# Power.net
KiCad netlist of a schematic drawn in Altium Designer
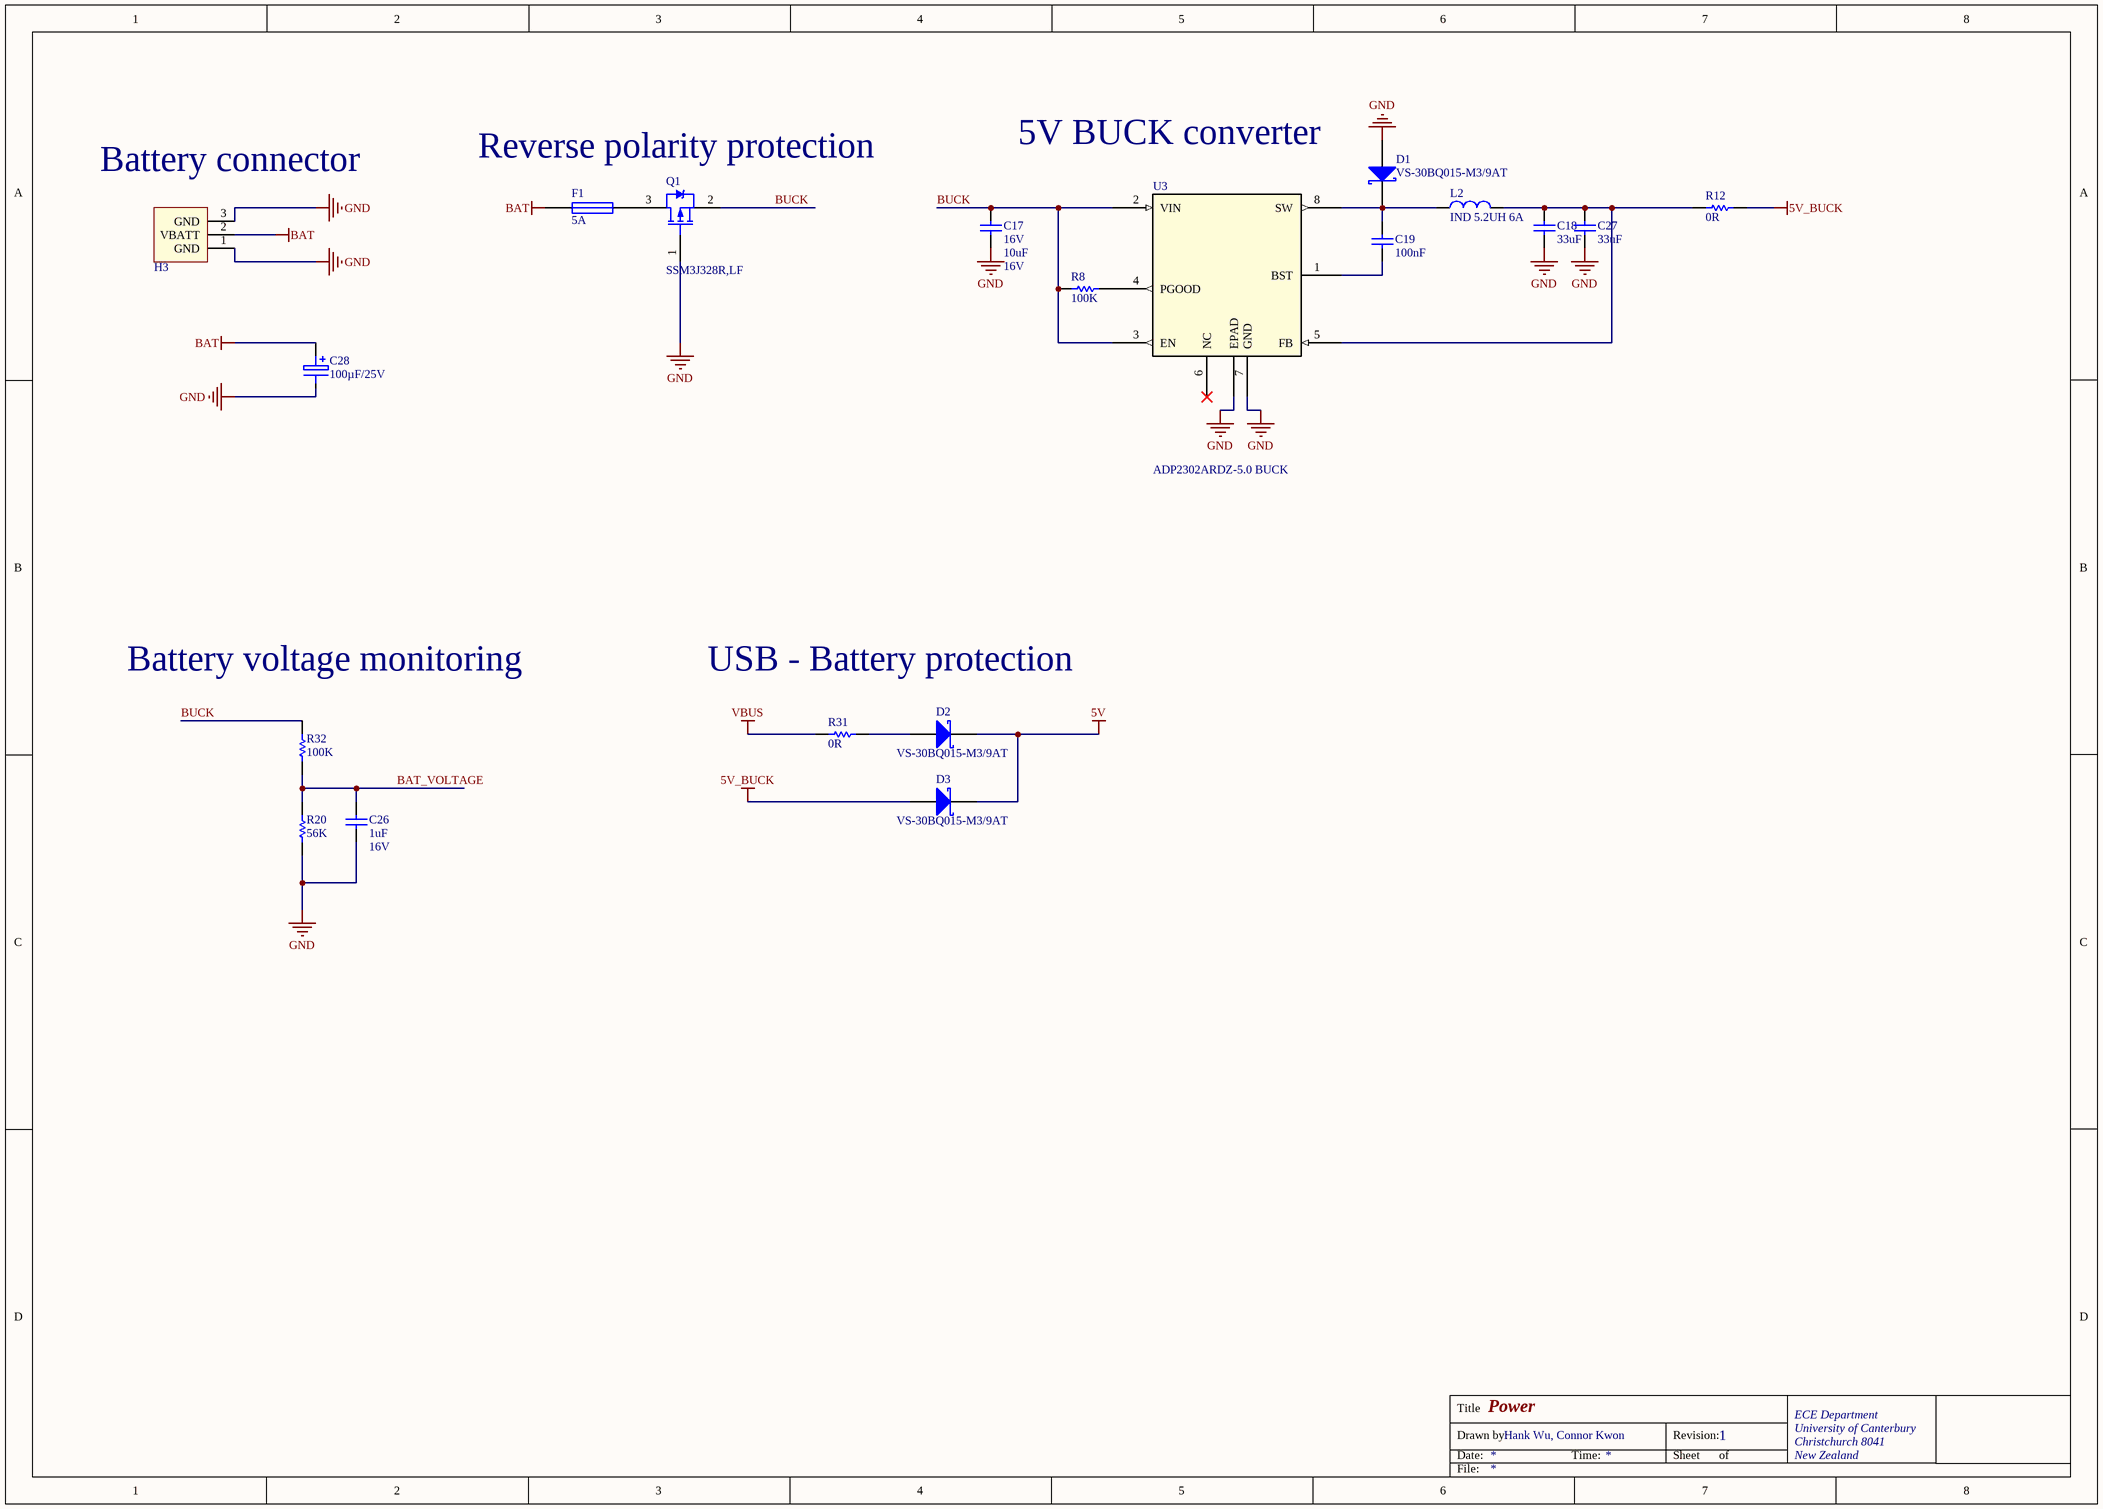
[diagram p0: Power.SchDoc]

(export (version "E")
  (design (tool "Eeschema 10.0.6"))
  (components
    (comp (ref "C17")
      (value "10uF")
      (footprint "CAPC2012L")
      (description "CAP CER 10uF X5R 16V 0805")
      (fields
        (field (name "MANUFACTURER") "Samsung Electro-Mechanics")
        (field (name "MANUFACTURER PART NUMBER") "CL21A106KOQNNWE")
        (field (name "VOLTAGE - RATED") "16V")
        (field (name "MAX VOLTAGE") "16V")
      )
      (libsource (lib "ENCE461AD19_19V2") (part "CC_10uF_16V_0805"))
    )
    (comp (ref "C18")
      (value "33uF")
      (footprint "CAPC2012L")
      (description "CAP CER 33uF X5R 6V3 0805")
      (fields
        (field (name "MANUFACTURER") "TDK Corporation")
        (field (name "MANUFACTURER PART NUMBER") "C2012X5R0J336M125AC")
      )
      (libsource (lib "ENCE461AD19_19V2") (part "CC_33uF_6V3_0805"))
    )
    (comp (ref "C19")
      (value "100nF")
      (footprint "CAPC1608L")
      (description "CAP CER 100nF X7R +-10% 50V 0603")
      (libsource (lib "ECE AD19Components_19V1") (part "CC_100nF_0603"))
    )
    (comp (ref "C26")
      (value "1uF")
      (footprint "CAPC1608L")
      (description "CAP CER 1uF Y5V -20% +80% 16V 0603")
      (fields (field (name "MAX VOLTAGE") "16V"))
      (libsource (lib "ECE AD19Components_19V1") (part "CC_1uF_0603"))
    )
    (comp (ref "C27")
      (value "33uF")
      (footprint "CAPC2012L")
      (description "CAP CER 33uF X5R 6V3 0805")
      (fields
        (field (name "MANUFACTURER") "TDK Corporation")
        (field (name "MANUFACTURER PART NUMBER") "C2012X5R0J336M125AC")
      )
      (libsource (lib "ENCE461AD19_19V2") (part "CC_33uF_6V3_0805"))
    )
    (comp (ref "C28")
      (value "100µF/25V")
      (footprint "CAPAE6666X77M")
      (description "CAP ALUM 100UF 25V 20% SMD")
      (fields
        (field (name "MANUFACTURER") "Nichicon")
        (field (name "MANUFACTURER PART NUMBER") "UWT1E101MCL1GS")
        (field (name "CAPACITANCE") "100µF/25V")
      )
      (libsource (lib "ECE AD19Components_19V1") (part "CA_100uF_25V"))
    )
    (comp (ref "D1")
      (value "VS-30BQ015-M3/9AT")
      (footprint "SMC")
      (description "DIODE, SCHOTTKY, 3A, 15V, DO-214AB / SMC")
      (fields (field (name "MANUFACTURER") "Vishay Semiconductors"))
      (libsource (lib "ECE AD19Components_19V1") (part "DS_VS-30BQ015-M3"))
    )
    (comp (ref "D2")
      (value "VS-30BQ015-M3/9AT")
      (footprint "SMC")
      (description "DIODE, SCHOTTKY, 3A, 15V, DO-214AB / SMC")
      (fields (field (name "MANUFACTURER") "Vishay Semiconductors"))
      (libsource (lib "ECE AD19Components_19V1") (part "DS_VS-30BQ015-M3"))
    )
    (comp (ref "D3")
      (value "VS-30BQ015-M3/9AT")
      (footprint "SMC")
      (description "DIODE, SCHOTTKY, 3A, 15V, DO-214AB / SMC")
      (fields (field (name "MANUFACTURER") "Vishay Semiconductors"))
      (libsource (lib "ECE AD19Components_19V1") (part "DS_VS-30BQ015-M3"))
    )
    (comp (ref "F1")
      (value "5A")
      (footprint "RESC3216N")
      (description "Fuse 5.0A Fast Acting 1206 SMD")
      (fields (field (name "MANUFACTURER PART NUMBER") "C1F5") (field (name "MANUFACTURER") "Bel TRP"))
      (libsource (lib "ECE AD19Components_19V1") (part "FS_Fuse_5.0A"))
    )
    (comp (ref "H3")
      (value "Battery_HEADER_3pin")
      (footprint "BATT_HEADER_3POS")
      (description "3Pin Header 2.54mm spacing")
      (libsource (lib "ENCE461AD19_19V2") (part "Battery_HEADER_3pin"))
    )
    (comp (ref "L2")
      (value "IND 5.2UH 6A")
      (footprint "INDUCTOR5u2")
      (description "FIXED IND 5.2UH 6A 22 MOHM SMD")
      (fields
        (field (name "MANUFACTURER") "Sumida America Components Inc.")
        (field (name "MANUFACTURER PART NUMBER") "CDRH104RNP-5R2NC")
      )
      (libsource (lib "ENCE461AD19_19V2") (part "CDRH104RNP-5R2NC"))
    )
    (comp (ref "Q1")
      (value "SSM3J328R,LF")
      (footprint "SOT23_L")
      (description "MOSFET P-CH 20V 6A SOT23-3")
      (fields
        (field (name "MANUFACTURER") "Toshiba")
        (field (name "MANUFACTURER PART NUMBER") "SSM3J328R,LF")
      )
      (libsource (lib "ECE AD19Components_19V1") (part "TM_SSM3J328R"))
    )
    (comp (ref "R8")
      (value "100K")
      (footprint "RESC1608L")
      (description "RES 100K OHM 1/10W 5% 0603 SMD")
      (libsource (lib "ECE AD19Components_19V1") (part "RS_100K"))
    )
    (comp (ref "R12")
      (value "0R")
      (footprint "RESC1608L")
      (description "RES 0.0 OHM 1/10W 5% 0603 SMD")
      (libsource (lib "ECE AD19Components_19V1") (part "RS_0R0"))
    )
    (comp (ref "R20")
      (value "56K")
      (footprint "RESC1608L")
      (description "RES 56.0K OHM 1/10W 5% 0603 SMD")
      (libsource (lib "ECE AD19Components_19V1") (part "RS_56K"))
    )
    (comp (ref "R31")
      (value "0R")
      (footprint "RESC1608L")
      (description "RES 0.0 OHM 1/10W 5% 0603 SMD")
      (libsource (lib "ECE AD19Components_19V1") (part "RS_0R0"))
    )
    (comp (ref "R32")
      (value "100K")
      (footprint "RESC1608L")
      (description "RES 100K OHM 1/10W 5% 0603 SMD")
      (libsource (lib "ECE AD19Components_19V1") (part "RS_100K"))
    )
    (comp (ref "U3")
      (value "ADP2302ARDZ-5.0 BUCK")
      (footprint "RD_8_1")
      (description "IC REG BUCK 5V 2A 8SOIC")
      (fields (field (name "MANUFACTURER_PART_NUMBER") "ADP2302ARDZ-5.0-R7"))
      (libsource (lib "ENCE461AD19_19V2") (part "ADP2302ARDZ-5.0-R7"))
    )
  )
  (nets
    (net (code "1") (name "/BAT_VOLTAGE") (class "Default")
      (node (ref "C26") (pin "2") (pinfunction "2_2") (pintype "passive"))
      (node (ref "R20") (pin "2") (pinfunction "2_2") (pintype "passive"))
      (node (ref "R32") (pin "1") (pinfunction "1_1") (pintype "passive"))
    )
    (net (code "2") (name "/BUCK") (class "Default")
      (node (ref "C17") (pin "2") (pinfunction "2_2") (pintype "passive"))
      (node (ref "Q1") (pin "2") (pinfunction "2_2") (pintype "passive"))
      (node (ref "R32") (pin "2") (pinfunction "2_2") (pintype "passive"))
      (node (ref "R8") (pin "1") (pinfunction "1_1") (pintype "passive"))
      (node (ref "U3") (pin "2") (pinfunction "VIN_2") (pintype "input"))
      (node (ref "U3") (pin "3") (pinfunction "EN_3") (pintype "output"))
    )
    (net (code "3") (name "5V") (class "Default")
      (node (ref "D2") (pin "2") (pinfunction "K_2") (pintype "passive"))
      (node (ref "D3") (pin "2") (pinfunction "K_2") (pintype "passive"))
    )
    (net (code "4") (name "5V_BUCK") (class "Default")
      (node (ref "D3") (pin "1") (pinfunction "A_1") (pintype "passive"))
      (node (ref "R12") (pin "2") (pinfunction "2_2") (pintype "passive"))
    )
    (net (code "5") (name "BAT") (class "Default")
      (node (ref "C28") (pin "2") (pintype "passive"))
      (node (ref "F1") (pin "1") (pinfunction "1_1") (pintype "passive"))
      (node (ref "H3") (pin "2") (pinfunction "VBATT_2") (pintype "passive"))
    )
    (net (code "6") (name "GND") (class "Default")
      (node (ref "C17") (pin "1") (pinfunction "1_1") (pintype "passive"))
      (node (ref "C18") (pin "1") (pinfunction "1_1") (pintype "passive"))
      (node (ref "C26") (pin "1") (pinfunction "1_1") (pintype "passive"))
      (node (ref "C27") (pin "1") (pinfunction "1_1") (pintype "passive"))
      (node (ref "C28") (pin "1") (pintype "passive"))
      (node (ref "D1") (pin "1") (pinfunction "A_1") (pintype "passive"))
      (node (ref "H3") (pin "1") (pinfunction "GND_1") (pintype "passive"))
      (node (ref "H3") (pin "3") (pinfunction "GND_3") (pintype "passive"))
      (node (ref "Q1") (pin "1") (pinfunction "1_1") (pintype "passive"))
      (node (ref "R20") (pin "1") (pinfunction "1_1") (pintype "passive"))
      (node (ref "U3") (pin "7") (pinfunction "GND_7") (pintype "power_in"))
      (node (ref "U3") (pin "EPAD") (pinfunction "EPAD_EPAD") (pintype "passive"))
    )
    (net (code "7") (name "Net-(D1-K)") (class "Default")
      (node (ref "C19") (pin "2") (pinfunction "2_2") (pintype "passive"))
      (node (ref "D1") (pin "2") (pinfunction "K_2") (pintype "passive"))
      (node (ref "L2") (pin "1") (pintype "passive"))
      (node (ref "U3") (pin "8") (pinfunction "SW_8") (pintype "output"))
    )
    (net (code "8") (name "Net-(D2-A)") (class "Default")
      (node (ref "D2") (pin "1") (pinfunction "A_1") (pintype "passive"))
      (node (ref "R31") (pin "2") (pinfunction "2_2") (pintype "passive"))
    )
    (net (code "9") (name "Net-(F1-Pad2)") (class "Default")
      (node (ref "F1") (pin "2") (pinfunction "2_2") (pintype "passive"))
      (node (ref "Q1") (pin "3") (pinfunction "3_3") (pintype "passive"))
    )
    (net (code "10") (name "Net-(U3-BST)") (class "Default")
      (node (ref "C19") (pin "1") (pinfunction "1_1") (pintype "passive"))
      (node (ref "U3") (pin "1") (pinfunction "BST_1") (pintype "passive"))
    )
    (net (code "11") (name "Net-(U3-FB)") (class "Default")
      (node (ref "C18") (pin "2") (pinfunction "2_2") (pintype "passive"))
      (node (ref "C27") (pin "2") (pinfunction "2_2") (pintype "passive"))
      (node (ref "L2") (pin "2") (pintype "passive"))
      (node (ref "R12") (pin "1") (pinfunction "1_1") (pintype "passive"))
      (node (ref "U3") (pin "5") (pinfunction "FB_5") (pintype "input"))
    )
    (net (code "12") (name "Net-(U3-PGOOD)") (class "Default")
      (node (ref "R8") (pin "2") (pinfunction "2_2") (pintype "passive"))
      (node (ref "U3") (pin "4") (pinfunction "PGOOD_4") (pintype "output"))
    )
    (net (code "13") (name "VBUS") (class "Default")
      (node (ref "R31") (pin "1") (pinfunction "1_1") (pintype "passive"))
    )
    (net (code "14") (name "unconnected-(U3-NC-Pad6)") (class "Default")
      (node (ref "U3") (pin "6") (pinfunction "NC_6") (pintype "passive+no_connect"))
    )
  )
)
